# bottom.net
KiCad netlist of a schematic drawn in EAGLE
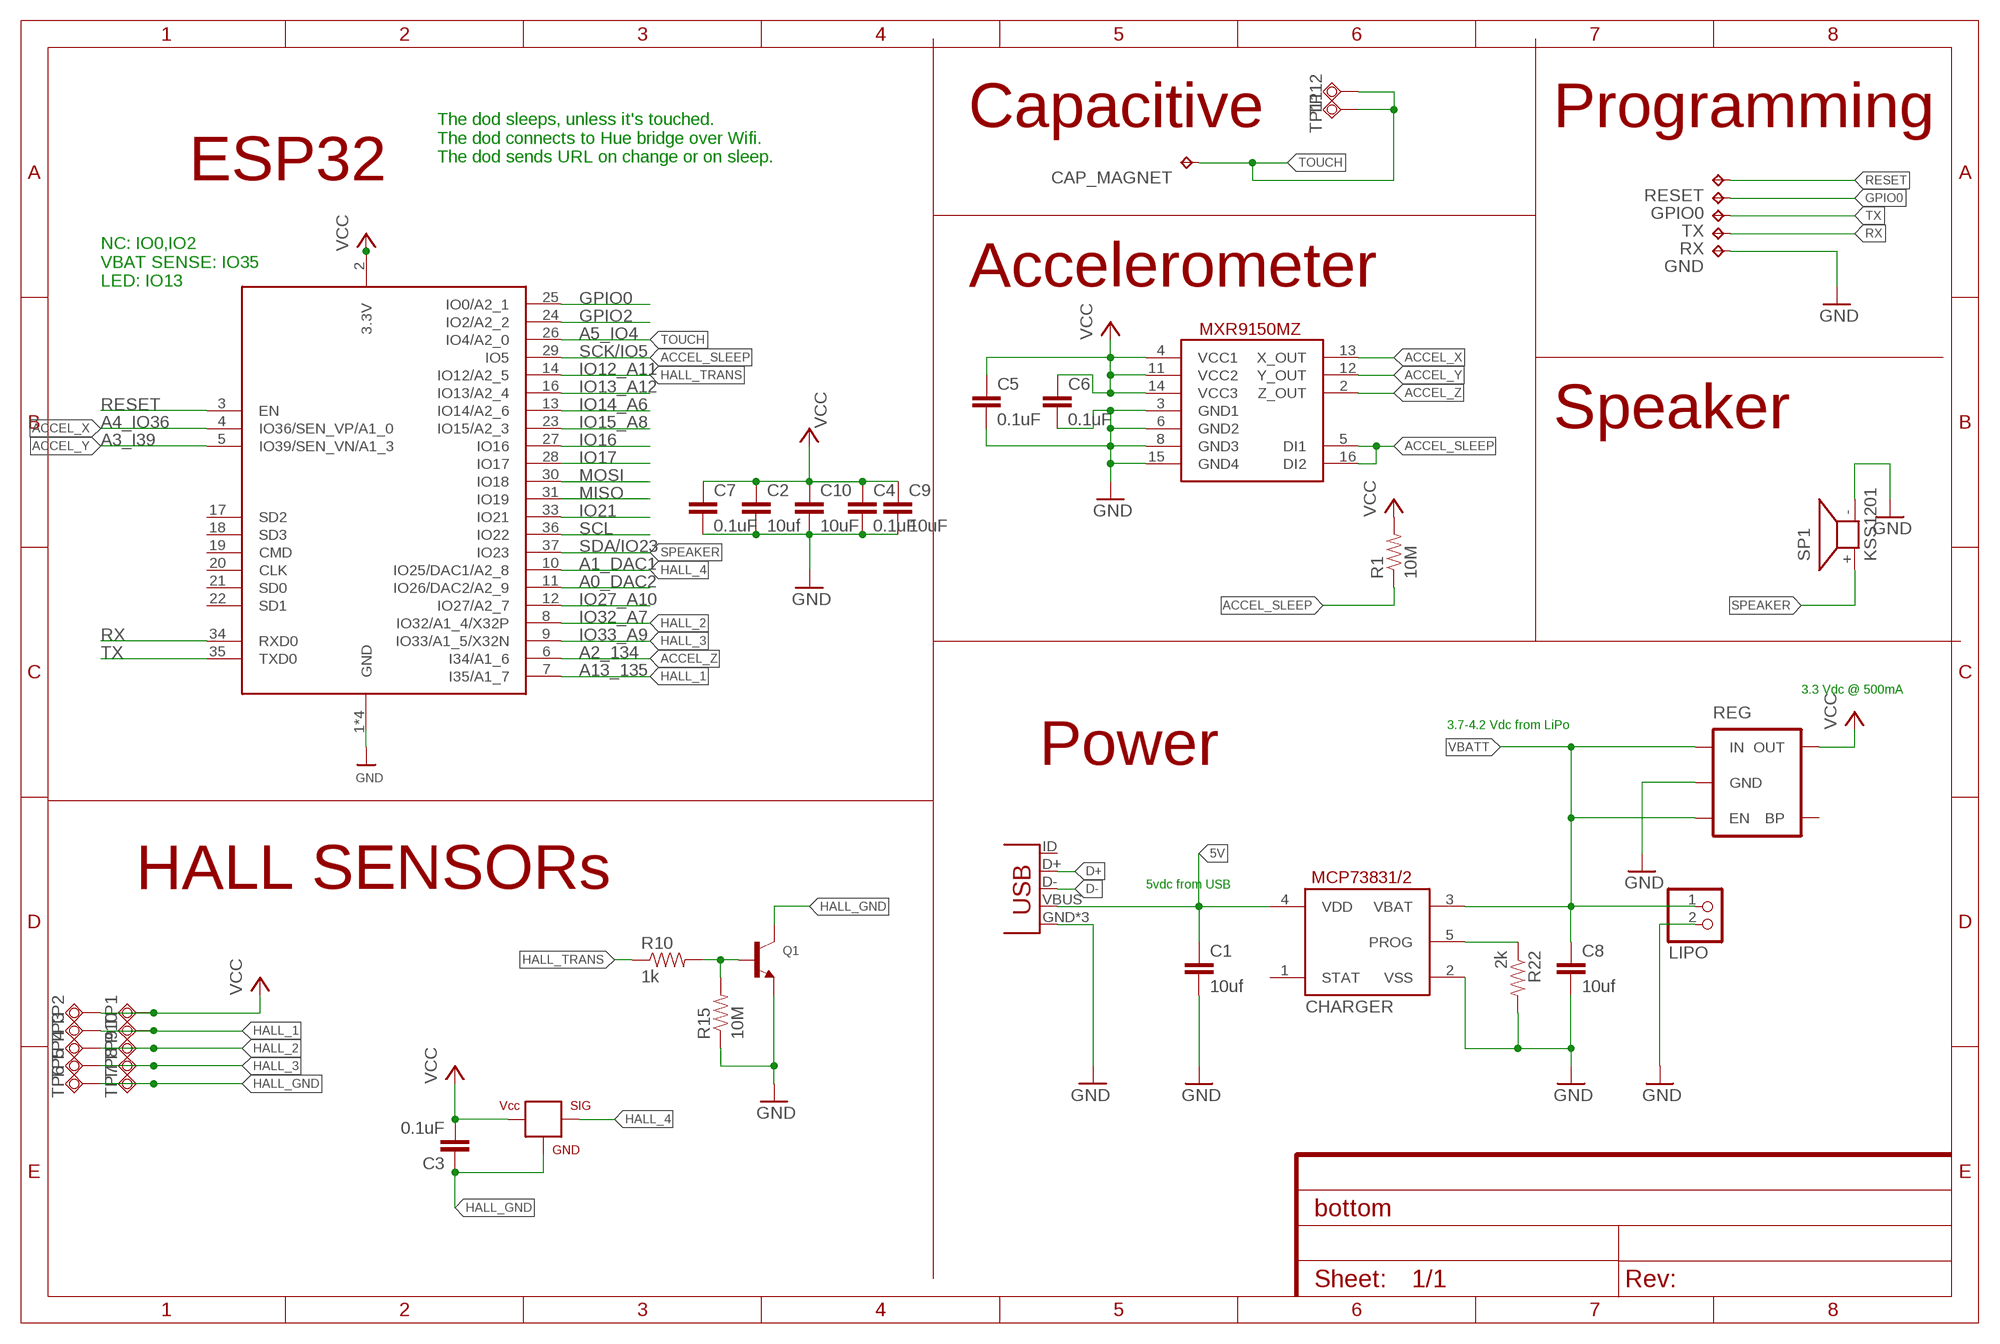
[diagram p0: schematic, sheet 1]

(export (version "E")
  (design (tool "Eeschema 10.0.6"))
  (components
    (comp (ref "C1")
      (value "10uf")
      (footprint "eagle-import:0603-CAP")
      (libsource (lib "eagle-import") (part "SparkFun-Capacitors_CAP0603-CAP"))
    )
    (comp (ref "C2")
      (value "10uf")
      (footprint "eagle-import:0402-CAP")
      (libsource (lib "eagle-import") (part "CAP0402-CAP"))
    )
    (comp (ref "C3")
      (value "0.1uF")
      (footprint "eagle-import:0603-CAP")
      (libsource (lib "eagle-import") (part "CAP0603-CAP"))
    )
    (comp (ref "C4")
      (value "0.1uF")
      (footprint "eagle-import:0402-CAP")
      (libsource (lib "eagle-import") (part "CAP0402-CAP"))
    )
    (comp (ref "C5")
      (value "0.1uF")
      (footprint "eagle-import:0402-CAP")
      (libsource (lib "eagle-import") (part "CAP0402-CAP"))
    )
    (comp (ref "C6")
      (value "0.1uF")
      (footprint "eagle-import:0402-CAP")
      (libsource (lib "eagle-import") (part "CAP0402-CAP"))
    )
    (comp (ref "C7")
      (value "0.1uF")
      (footprint "eagle-import:0402-CAP")
      (libsource (lib "eagle-import") (part "CAP0402-CAP"))
    )
    (comp (ref "C8")
      (value "10uf")
      (footprint "eagle-import:0603-CAP")
      (libsource (lib "eagle-import") (part "SparkFun-Capacitors_CAP0603-CAP"))
    )
    (comp (ref "C9")
      (value "10uF")
      (footprint "eagle-import:0402-CAP")
      (libsource (lib "eagle-import") (part "CAP0402-CAP"))
    )
    (comp (ref "C10")
      (value "10uF")
      (footprint "eagle-import:0402-CAP")
      (libsource (lib "eagle-import") (part "CAP0402-CAP"))
    )
    (comp (ref "CAP_MAGNET")
      (value "TPTP10R")
      (footprint "eagle-import:TP10R")
      (libsource (lib "eagle-import") (part "TPTP10R"))
    )
    (comp (ref "CHARGER")
      (value "MCP73831/OT")
      (footprint "eagle-import:SOT23-5L")
      (libsource (lib "eagle-import") (part "MCP73831/OT"))
    )
    (comp (ref "GND")
      (value "TPTP13SQ")
      (footprint "eagle-import:TP13SQ")
      (libsource (lib "eagle-import") (part "TPTP13SQ"))
    )
    (comp (ref "GPIO0")
      (value "TPTP13R")
      (footprint "eagle-import:TP13R")
      (libsource (lib "eagle-import") (part "TPTP13R"))
    )
    (comp (ref "HALL")
      (value "A1304")
      (footprint "eagle-import:SOT23-3")
      (libsource (lib "eagle-import") (part "HALLEFFECT-A1326"))
    )
    (comp (ref "JP1")
      (value "USB-MICROB")
      (footprint "eagle-import:USB-MICROB")
      (libsource (lib "eagle-import") (part "USB-MICROB"))
    )
    (comp (ref "LIPO")
      (value "JST_2PIN-THM")
      (footprint "eagle-import:JST-PH-2-THM")
      (libsource (lib "eagle-import") (part "JST_2PIN-THM"))
    )
    (comp (ref "Q1")
      (value "TRANSISTOR_NPN")
      (footprint "eagle-import:SOT-23-R")
      (libsource (lib "eagle-import") (part "TRANSISTOR_NPN"))
    )
    (comp (ref "R1")
      (value "10M")
      (footprint "eagle-import:0402-RES")
      (libsource (lib "eagle-import") (part "RESISTOR0402-RES"))
    )
    (comp (ref "R10")
      (value "1k")
      (footprint "eagle-import:0402-RES")
      (libsource (lib "eagle-import") (part "RESISTOR0402-RES"))
    )
    (comp (ref "R15")
      (value "10M")
      (footprint "eagle-import:0402-RES")
      (libsource (lib "eagle-import") (part "RESISTOR0402-RES"))
    )
    (comp (ref "R22")
      (value "2k")
      (footprint "eagle-import:0402-RES")
      (libsource (lib "eagle-import") (part "RESISTOR0402-RES"))
    )
    (comp (ref "REG")
      (value "MIC52053.3V")
      (footprint "eagle-import:SOT23-5")
      (libsource (lib "eagle-import") (part "MIC52053.3V"))
    )
    (comp (ref "RESET")
      (value "TPTP13R")
      (footprint "eagle-import:TP13R")
      (libsource (lib "eagle-import") (part "TPTP13R"))
    )
    (comp (ref "RX")
      (value "TPTP13R")
      (footprint "eagle-import:TP13R")
      (libsource (lib "eagle-import") (part "TPTP13R"))
    )
    (comp (ref "SP1")
      (value "KSS1201")
      (footprint "eagle-import:KSS1201")
      (libsource (lib "eagle-import") (part "KSS1201"))
    )
    (comp (ref "TP1")
      (value "TPSQTP10SQ")
      (footprint "eagle-import:TP10SQ")
      (libsource (lib "eagle-import") (part "TPSQTP10SQ"))
    )
    (comp (ref "TP2")
      (value "TPSQTP10SQ")
      (footprint "eagle-import:TP10SQ")
      (libsource (lib "eagle-import") (part "TPSQTP10SQ"))
    )
    (comp (ref "TP3")
      (value "TPSQTP10SQ")
      (footprint "eagle-import:TP10SQ")
      (libsource (lib "eagle-import") (part "TPSQTP10SQ"))
    )
    (comp (ref "TP4")
      (value "TPSQTP10SQ")
      (footprint "eagle-import:TP10SQ")
      (libsource (lib "eagle-import") (part "TPSQTP10SQ"))
    )
    (comp (ref "TP5")
      (value "TPSQTP10SQ")
      (footprint "eagle-import:TP10SQ")
      (libsource (lib "eagle-import") (part "TPSQTP10SQ"))
    )
    (comp (ref "TP6")
      (value "TPSQTP10SQ")
      (footprint "eagle-import:TP10SQ")
      (libsource (lib "eagle-import") (part "TPSQTP10SQ"))
    )
    (comp (ref "TP7")
      (value "TPSQTP10SQ")
      (footprint "eagle-import:TP10SQ")
      (libsource (lib "eagle-import") (part "TPSQTP10SQ"))
    )
    (comp (ref "TP8")
      (value "TPSQTP10SQ")
      (footprint "eagle-import:TP10SQ")
      (libsource (lib "eagle-import") (part "TPSQTP10SQ"))
    )
    (comp (ref "TP9")
      (value "TPSQTP10SQ")
      (footprint "eagle-import:TP10SQ")
      (libsource (lib "eagle-import") (part "TPSQTP10SQ"))
    )
    (comp (ref "TP10")
      (value "TPSQTP10SQ")
      (footprint "eagle-import:TP10SQ")
      (libsource (lib "eagle-import") (part "TPSQTP10SQ"))
    )
    (comp (ref "TP11")
      (value "TPSQTP10SQ")
      (footprint "eagle-import:TP10SQ")
      (libsource (lib "eagle-import") (part "TPSQTP10SQ"))
    )
    (comp (ref "TP12")
      (value "TPSQTP10SQ")
      (footprint "eagle-import:TP10SQ")
      (libsource (lib "eagle-import") (part "TPSQTP10SQ"))
    )
    (comp (ref "TX")
      (value "TPTP13R")
      (footprint "eagle-import:TP13R")
      (libsource (lib "eagle-import") (part "TPTP13R"))
    )
    (comp (ref "U$1")
      (value "ACCELEROMETER_MXR9150MZ")
      (footprint "eagle-import:MXR9150MZ")
      (libsource (lib "eagle-import") (part "ACCELEROMETER_MXR9150MZ"))
    )
    (comp (ref "X2")
      (value "ESP32_WROOM32_SKINNY")
      (footprint "eagle-import:WROOM32_SKINNY")
      (libsource (lib "eagle-import") (part "ESP32_WROOM32_SKINNY"))
    )
  )
  (nets
    (net (code "1") (name "/A0_DAC2") (class "Default")
      (node (ref "X2") (pin "11") (pinfunction "IO26/DAC2/A2_9_11") (pintype "bidirectional"))
    )
    (net (code "2") (name "/GPIO2") (class "Default")
      (node (ref "X2") (pin "24") (pinfunction "IO2/A2_2_24") (pintype "bidirectional"))
    )
    (net (code "3") (name "/IO16") (class "Default")
      (node (ref "X2") (pin "27") (pinfunction "IO16_27") (pintype "bidirectional"))
    )
    (net (code "4") (name "/IO17") (class "Default")
      (node (ref "X2") (pin "28") (pinfunction "IO17_28") (pintype "bidirectional"))
    )
    (net (code "5") (name "/IO21") (class "Default")
      (node (ref "X2") (pin "33") (pinfunction "IO21_33") (pintype "bidirectional"))
    )
    (net (code "6") (name "/MISO") (class "Default")
      (node (ref "X2") (pin "31") (pinfunction "IO19_31") (pintype "bidirectional"))
    )
    (net (code "7") (name "/MOSI") (class "Default")
      (node (ref "X2") (pin "30") (pinfunction "IO18_30") (pintype "bidirectional"))
    )
    (net (code "8") (name "/SCL") (class "Default")
      (node (ref "X2") (pin "36") (pinfunction "IO22_36") (pintype "bidirectional"))
    )
    (net (code "9") (name "5V") (class "Default")
      (node (ref "C1") (pin "1") (pinfunction "1_1") (pintype "passive"))
      (node (ref "CHARGER") (pin "4") (pinfunction "VDD_4") (pintype "power_in"))
      (node (ref "JP1") (pin "VBUS") (pinfunction "VBUS_VBUS") (pintype "bidirectional"))
    )
    (net (code "10") (name "ACCEL_SLEEP") (class "Default")
      (node (ref "R1") (pin "1") (pinfunction "1_1") (pintype "passive"))
      (node (ref "U$1") (pin "16") (pinfunction "DI2_16") (pintype "bidirectional"))
      (node (ref "U$1") (pin "5") (pinfunction "DI1_5") (pintype "bidirectional"))
      (node (ref "X2") (pin "29") (pinfunction "IO5_29") (pintype "bidirectional"))
    )
    (net (code "11") (name "ACCEL_X") (class "Default")
      (node (ref "U$1") (pin "13") (pinfunction "X_OUT_13") (pintype "bidirectional"))
      (node (ref "X2") (pin "4") (pinfunction "IO36/SEN_VP/A1_0_4") (pintype "passive"))
    )
    (net (code "12") (name "ACCEL_Y") (class "Default")
      (node (ref "U$1") (pin "12") (pinfunction "Y_OUT_12") (pintype "bidirectional"))
      (node (ref "X2") (pin "5") (pinfunction "IO39/SEN_VN/A1_3_5") (pintype "passive"))
    )
    (net (code "13") (name "ACCEL_Z") (class "Default")
      (node (ref "U$1") (pin "2") (pinfunction "Z_OUT_2") (pintype "bidirectional"))
      (node (ref "X2") (pin "6") (pinfunction "I34/A1_6_6") (pintype "bidirectional"))
    )
    (net (code "14") (name "D+") (class "Default")
      (node (ref "JP1") (pin "D+") (pinfunction "D+_D+") (pintype "bidirectional"))
    )
    (net (code "15") (name "D-") (class "Default")
      (node (ref "JP1") (pin "D-") (pinfunction "D-_D-") (pintype "bidirectional"))
    )
    (net (code "16") (name "GND") (class "Default")
      (node (ref "C1") (pin "2") (pinfunction "2_2") (pintype "passive"))
      (node (ref "C10") (pin "2") (pinfunction "2_2") (pintype "passive"))
      (node (ref "C2") (pin "2") (pinfunction "2_2") (pintype "passive"))
      (node (ref "C4") (pin "2") (pinfunction "2_2") (pintype "passive"))
      (node (ref "C5") (pin "2") (pinfunction "2_2") (pintype "passive"))
      (node (ref "C6") (pin "2") (pinfunction "2_2") (pintype "passive"))
      (node (ref "C7") (pin "2") (pinfunction "2_2") (pintype "passive"))
      (node (ref "C8") (pin "2") (pinfunction "2_2") (pintype "passive"))
      (node (ref "C9") (pin "2") (pinfunction "2_2") (pintype "passive"))
      (node (ref "CHARGER") (pin "2") (pinfunction "VSS_2") (pintype "power_in"))
      (node (ref "GND") (pin "TP") (pinfunction "TP_TP") (pintype "input"))
      (node (ref "JP1") (pin "GND") (pinfunction "GND_GND") (pintype "bidirectional"))
      (node (ref "JP1") (pin "MT1") (pinfunction "GND_MT1") (pintype "bidirectional"))
      (node (ref "JP1") (pin "MT2") (pinfunction "GND_MT2") (pintype "bidirectional"))
      (node (ref "LIPO") (pin "2") (pinfunction "1_2") (pintype "passive"))
      (node (ref "Q1") (pin "3-EMITTER") (pinfunction "E_3-EMITTER") (pintype "passive"))
      (node (ref "R15") (pin "1") (pinfunction "1_1") (pintype "passive"))
      (node (ref "R22") (pin "2") (pinfunction "2_2") (pintype "passive"))
      (node (ref "REG") (pin "2") (pinfunction "GND_2") (pintype "input"))
      (node (ref "SP1") (pin "-") (pinfunction "2_-") (pintype "passive"))
      (node (ref "U$1") (pin "15") (pinfunction "GND4_15") (pintype "bidirectional"))
      (node (ref "U$1") (pin "3") (pinfunction "GND1_3") (pintype "bidirectional"))
      (node (ref "U$1") (pin "6") (pinfunction "GND2_6") (pintype "bidirectional"))
      (node (ref "U$1") (pin "8") (pinfunction "GND3_8") (pintype "bidirectional"))
      (node (ref "X2") (pin "1") (pinfunction "GND_1") (pintype "passive"))
      (node (ref "X2") (pin "15") (pinfunction "GND_15") (pintype "passive"))
      (node (ref "X2") (pin "38") (pinfunction "GND_38") (pintype "passive"))
      (node (ref "X2") (pin "P$1") (pinfunction "GND_P$1") (pintype "passive"))
    )
    (net (code "17") (name "GPIO0") (class "Default")
      (node (ref "GPIO0") (pin "TP") (pinfunction "TP_TP") (pintype "input"))
      (node (ref "X2") (pin "25") (pinfunction "IO0/A2_1_25") (pintype "bidirectional"))
    )
    (net (code "18") (name "HALL_1") (class "Default")
      (node (ref "TP10") (pin "TP") (pinfunction "TP_TP") (pintype "input"))
      (node (ref "TP3") (pin "TP") (pinfunction "TP_TP") (pintype "input"))
      (node (ref "X2") (pin "7") (pinfunction "I35/A1_7_7") (pintype "bidirectional"))
    )
    (net (code "19") (name "HALL_2") (class "Default")
      (node (ref "TP4") (pin "TP") (pinfunction "TP_TP") (pintype "input"))
      (node (ref "TP9") (pin "TP") (pinfunction "TP_TP") (pintype "input"))
      (node (ref "X2") (pin "8") (pinfunction "IO32/A1_4/X32P_8") (pintype "bidirectional"))
    )
    (net (code "20") (name "HALL_3") (class "Default")
      (node (ref "TP5") (pin "TP") (pinfunction "TP_TP") (pintype "input"))
      (node (ref "TP8") (pin "TP") (pinfunction "TP_TP") (pintype "input"))
      (node (ref "X2") (pin "9") (pinfunction "IO33/A1_5/X32N_9") (pintype "bidirectional"))
    )
    (net (code "21") (name "HALL_4") (class "Default")
      (node (ref "HALL") (pin "2") (pinfunction "SIG_2") (pintype "bidirectional"))
      (node (ref "X2") (pin "10") (pinfunction "IO25/DAC1/A2_8_10") (pintype "bidirectional"))
    )
    (net (code "22") (name "HALL_GND") (class "Default")
      (node (ref "C3") (pin "1") (pinfunction "1_1") (pintype "passive"))
      (node (ref "HALL") (pin "3") (pinfunction "GND_3") (pintype "bidirectional"))
      (node (ref "Q1") (pin "2-COLLECTOR") (pinfunction "C_2-COLLECTOR") (pintype "passive"))
      (node (ref "TP6") (pin "TP") (pinfunction "TP_TP") (pintype "input"))
      (node (ref "TP7") (pin "TP") (pinfunction "TP_TP") (pintype "input"))
    )
    (net (code "23") (name "HALL_TRANS") (class "Default")
      (node (ref "R10") (pin "1") (pinfunction "1_1") (pintype "passive"))
      (node (ref "X2") (pin "14") (pinfunction "IO12/A2_5_14") (pintype "bidirectional"))
    )
    (net (code "24") (name "Net-(CHARGER-PROG)") (class "Default")
      (node (ref "CHARGER") (pin "5") (pinfunction "PROG_5") (pintype "input"))
      (node (ref "R22") (pin "1") (pinfunction "1_1") (pintype "passive"))
    )
    (net (code "25") (name "Net-(Q1-B)") (class "Default")
      (node (ref "Q1") (pin "1-BASE") (pinfunction "B_1-BASE") (pintype "passive"))
      (node (ref "R10") (pin "2") (pinfunction "2_2") (pintype "passive"))
      (node (ref "R15") (pin "2") (pinfunction "2_2") (pintype "passive"))
    )
    (net (code "26") (name "RESET") (class "Default")
      (node (ref "RESET") (pin "TP") (pinfunction "TP_TP") (pintype "input"))
      (node (ref "X2") (pin "3") (pinfunction "EN_3") (pintype "input"))
    )
    (net (code "27") (name "RX") (class "Default")
      (node (ref "RX") (pin "TP") (pinfunction "TP_TP") (pintype "input"))
      (node (ref "X2") (pin "34") (pinfunction "RXD0_34") (pintype "input"))
    )
    (net (code "28") (name "SPEAKER") (class "Default")
      (node (ref "SP1") (pin "+") (pinfunction "1_+") (pintype "passive"))
      (node (ref "X2") (pin "37") (pinfunction "IO23_37") (pintype "bidirectional"))
    )
    (net (code "29") (name "TOUCH") (class "Default")
      (node (ref "CAP_MAGNET") (pin "TP") (pinfunction "TP_TP") (pintype "input"))
      (node (ref "TP11") (pin "TP") (pinfunction "TP_TP") (pintype "input"))
      (node (ref "TP12") (pin "TP") (pinfunction "TP_TP") (pintype "input"))
      (node (ref "X2") (pin "26") (pinfunction "IO4/A2_0_26") (pintype "bidirectional"))
    )
    (net (code "30") (name "TX") (class "Default")
      (node (ref "TX") (pin "TP") (pinfunction "TP_TP") (pintype "input"))
      (node (ref "X2") (pin "35") (pinfunction "TXD0_35") (pintype "output"))
    )
    (net (code "31") (name "VBATT") (class "Default")
      (node (ref "C8") (pin "1") (pinfunction "1_1") (pintype "passive"))
      (node (ref "CHARGER") (pin "3") (pinfunction "VBAT_3") (pintype "bidirectional"))
      (node (ref "LIPO") (pin "1") (pinfunction "2_1") (pintype "passive"))
      (node (ref "REG") (pin "1") (pinfunction "IN_1") (pintype "input"))
      (node (ref "REG") (pin "3") (pinfunction "EN_3") (pintype "input"))
    )
    (net (code "32") (name "VCC") (class "Default")
      (node (ref "C10") (pin "1") (pinfunction "1_1") (pintype "passive"))
      (node (ref "C2") (pin "1") (pinfunction "1_1") (pintype "passive"))
      (node (ref "C3") (pin "2") (pinfunction "2_2") (pintype "passive"))
      (node (ref "C4") (pin "1") (pinfunction "1_1") (pintype "passive"))
      (node (ref "C5") (pin "1") (pinfunction "1_1") (pintype "passive"))
      (node (ref "C6") (pin "1") (pinfunction "1_1") (pintype "passive"))
      (node (ref "C7") (pin "1") (pinfunction "1_1") (pintype "passive"))
      (node (ref "C9") (pin "1") (pinfunction "1_1") (pintype "passive"))
      (node (ref "HALL") (pin "1") (pinfunction "VCC_1") (pintype "bidirectional"))
      (node (ref "R1") (pin "2") (pinfunction "2_2") (pintype "passive"))
      (node (ref "REG") (pin "5") (pinfunction "OUT_5") (pintype "passive"))
      (node (ref "TP1") (pin "TP") (pinfunction "TP_TP") (pintype "input"))
      (node (ref "TP2") (pin "TP") (pinfunction "TP_TP") (pintype "input"))
      (node (ref "U$1") (pin "11") (pinfunction "VCC2_11") (pintype "bidirectional"))
      (node (ref "U$1") (pin "14") (pinfunction "VCC3_14") (pintype "bidirectional"))
      (node (ref "U$1") (pin "4") (pinfunction "VCC1_4") (pintype "bidirectional"))
      (node (ref "X2") (pin "2") (pinfunction "3.3V_2") (pintype "passive"))
    )
    (net (code "33") (name "unconnected-(CHARGER-STAT-Pad1)") (class "Default")
      (node (ref "CHARGER") (pin "1") (pinfunction "STAT_1") (pintype "output"))
    )
    (net (code "34") (name "unconnected-(JP1-SHIELD-PadID)") (class "Default")
      (node (ref "JP1") (pin "ID") (pinfunction "SHIELD_ID") (pintype "bidirectional"))
    )
    (net (code "35") (name "unconnected-(REG-BP-Pad4)") (class "Default")
      (node (ref "REG") (pin "4") (pinfunction "BP_4") (pintype "input"))
    )
    (net (code "36") (name "unconnected-(X2-CLK-Pad20)") (class "Default")
      (node (ref "X2") (pin "20") (pinfunction "CLK_20") (pintype "bidirectional"))
    )
    (net (code "37") (name "unconnected-(X2-CMD-Pad19)") (class "Default")
      (node (ref "X2") (pin "19") (pinfunction "CMD_19") (pintype "bidirectional"))
    )
    (net (code "38") (name "unconnected-(X2-IO13{slash}A2_4-Pad16)") (class "Default")
      (node (ref "X2") (pin "16") (pinfunction "IO13/A2_4_16") (pintype "bidirectional"))
    )
    (net (code "39") (name "unconnected-(X2-IO14{slash}A2_6-Pad13)") (class "Default")
      (node (ref "X2") (pin "13") (pinfunction "IO14/A2_6_13") (pintype "bidirectional"))
    )
    (net (code "40") (name "unconnected-(X2-IO15{slash}A2_3-Pad23)") (class "Default")
      (node (ref "X2") (pin "23") (pinfunction "IO15/A2_3_23") (pintype "bidirectional"))
    )
    (net (code "41") (name "unconnected-(X2-IO27{slash}A2_7-Pad12)") (class "Default")
      (node (ref "X2") (pin "12") (pinfunction "IO27/A2_7_12") (pintype "bidirectional"))
    )
    (net (code "42") (name "unconnected-(X2-SD0-Pad21)") (class "Default")
      (node (ref "X2") (pin "21") (pinfunction "SD0_21") (pintype "bidirectional"))
    )
    (net (code "43") (name "unconnected-(X2-SD1-Pad22)") (class "Default")
      (node (ref "X2") (pin "22") (pinfunction "SD1_22") (pintype "bidirectional"))
    )
    (net (code "44") (name "unconnected-(X2-SD2-Pad17)") (class "Default")
      (node (ref "X2") (pin "17") (pinfunction "SD2_17") (pintype "bidirectional"))
    )
    (net (code "45") (name "unconnected-(X2-SD3-Pad18)") (class "Default")
      (node (ref "X2") (pin "18") (pinfunction "SD3_18") (pintype "bidirectional"))
    )
  )
)
